# Sheet1.net
KiCad netlist of a schematic drawn in Altium Designer
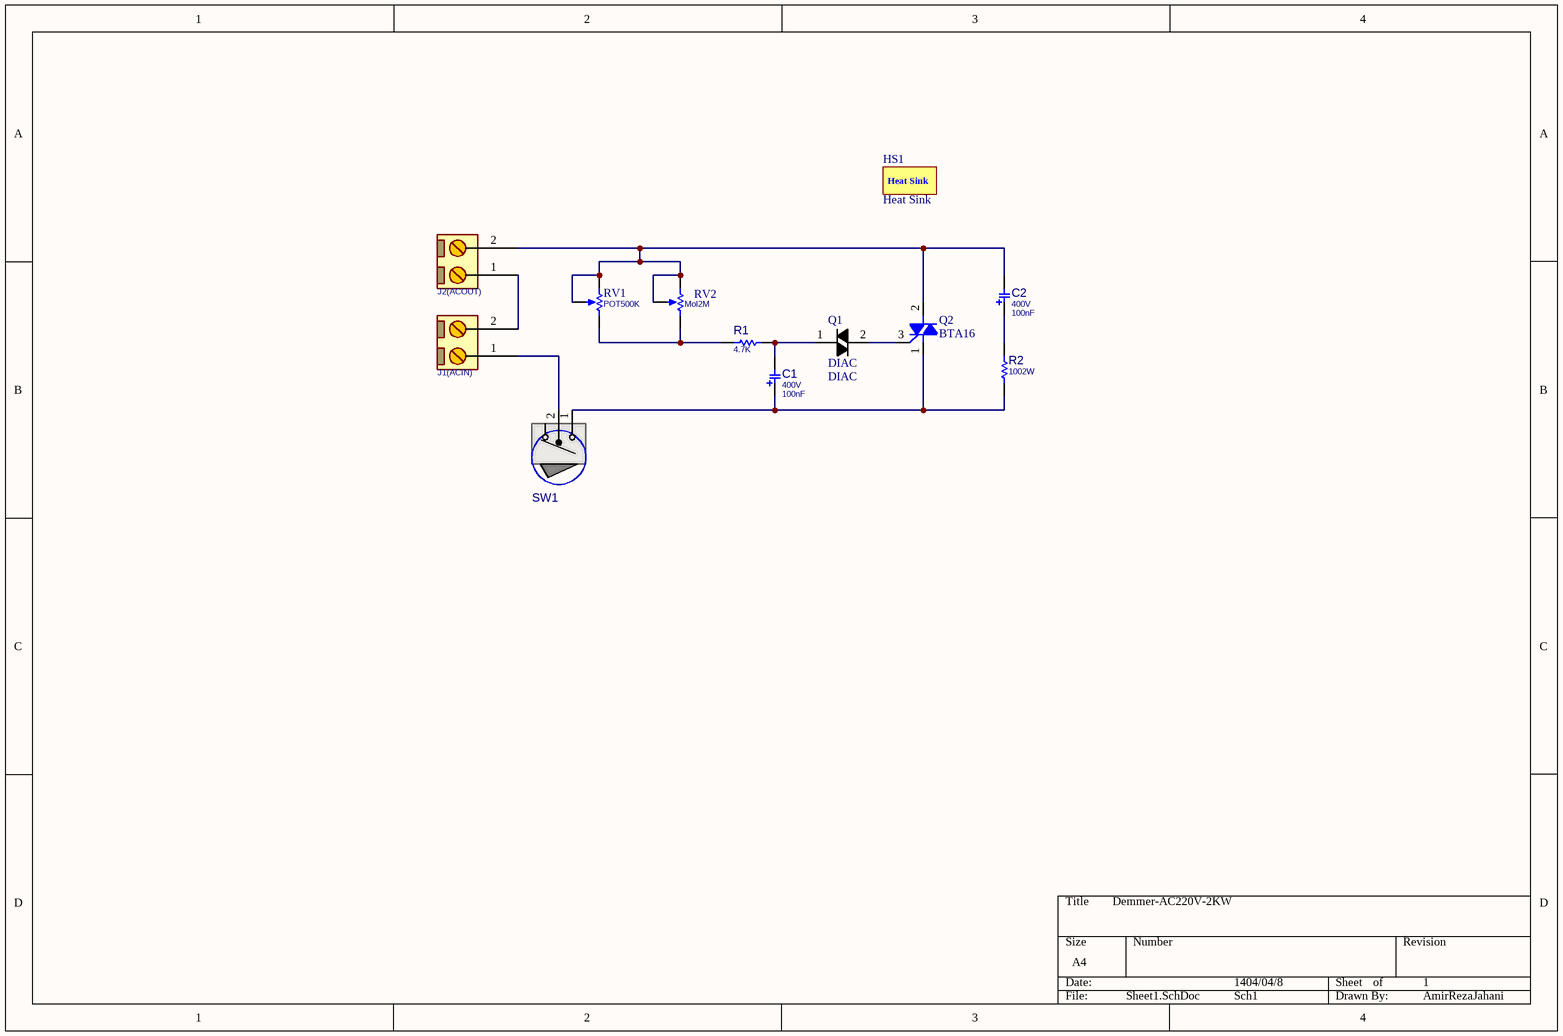
[diagram p0: Sheet1.SchDoc]

(export (version "E")
  (design (tool "Eeschema 10.0.6"))
  (components
    (comp (ref "C1")
      (value "100nF")
      (footprint "C_FLM_22X7H14")
      (description "CAP, THD, FILM,")
      (fields
        (field (name "MANF_P#") "MANF_PART#")
        (field (name "MANF") "MANF")
        (field (name "PARAM2") "400V")
      )
      (libsource (lib "passive_thd") (part "CAP_THD_FLM_0.33uF_400v"))
    )
    (comp (ref "C2")
      (value "100nF")
      (footprint "C_FLM_22X7H14")
      (description "CAP, THD, FILM,")
      (fields
        (field (name "MANF_P#") "MANF_PART#")
        (field (name "MANF") "MANF")
        (field (name "PARAM2") "400V")
      )
      (libsource (lib "passive_thd") (part "CAP_THD_FLM_0.33uF_400v"))
    )
    (comp (ref "HS1")
      (value "Heat Sink")
      (footprint "HeatSink PH51")
      (description "PH51 Heatsink")
      (libsource (lib "My_Library") (part "HeatSink PH51"))
    )
    (comp (ref "J1(ACIN)")
      (value "CONN_TB2")
      (footprint "TBG_2")
      (description "CONN, TERMINAL BLOCK, 5.08mm pitch")
      (libsource (lib "conn_terminalB") (part "CONN_TB2"))
    )
    (comp (ref "J2(ACOUT)")
      (value "CONN_TB2")
      (footprint "TBG_2")
      (description "CONN, TERMINAL BLOCK, 5.08mm pitch")
      (libsource (lib "conn_terminalB") (part "CONN_TB2"))
    )
    (comp (ref "Q1")
      (value "DIAC")
      (footprint "D_AX03_DO35")
      (description "Diac, 32VBO, DO-35")
      (fields (field (name "MANF_P#") "DB3") (field (name "MANF") "ST") (field (name "ALTIUM_VALUE") "DIAC"))
      (libsource (lib "triac_diac") (part "DIAC_DB3_DO35"))
    )
    (comp (ref "Q2")
      (value "BTA16")
      (footprint "TO220_3")
      (description "Triac, 800V, 16A, TO-220")
      (fields (field (name "MANF_P#") "BTA16-800CW") (field (name "MANF") "ST"))
      (libsource (lib "triac_diac") (part "TRIAC_BTA16-800_TO220"))
    )
    (comp (ref "R1")
      (value "4.7K")
      (footprint "R025W_AX04")
      (description "RESISTOR, THD")
      (fields (field (name "MANF_P#") "RK73H1ETTP4701F") (field (name "MANF") "KOA SPEER"))
      (libsource (lib "passive_thd") (part "RES_THD"))
    )
    (comp (ref "R2")
      (value "1002W")
      (footprint "R2W_AX08")
      (description "RESISTOR, THD")
      (fields (field (name "MANF_P#") "RK73H1ETTP4701F") (field (name "MANF") "KOA SPEER"))
      (libsource (lib "passive_thd") (part "RES_THD"))
    )
    (comp (ref "RV1")
      (value "POT500K")
      (footprint "VOL_R")
      (description "RESISTOR, THD, Potentiometer Volume")
      (libsource (lib "resistor_pot_trimmer") (part "RES_THD_POT_VOL"))
    )
    (comp (ref "RV2")
      (value "Mol2M")
      (footprint "POT_3296W")
      (description "RESISTOR, THD, Potentiometer")
      (libsource (lib "resistor_pot_trimmer") (part "RES_THD_POT_3296W"))
    )
    (comp (ref "SW1")
      (value "ToggleSwitch")
      (footprint "SWRCK_SPST_S_15X10")
      (description "SWITCH, Rocker, SPST, THD, 15x10.5mm")
      (libsource (lib "switch_rocker") (part "SWROK_SPST_R_15X10"))
    )
  )
  (nets
    (net (code "1") (name "Net-(C2-Pad1)") (class "Default")
      (node (ref "C2") (pin "1") (pinfunction "1_1") (pintype "passive"))
      (node (ref "R2") (pin "2") (pinfunction "2_2") (pintype "passive"))
    )
    (net (code "2") (name "Net-(J1(ACIN)-Pad2)") (class "Default")
      (node (ref "J1(ACIN)") (pin "2") (pinfunction "2_2") (pintype "passive"))
      (node (ref "J2(ACOUT)") (pin "1") (pinfunction "1_1") (pintype "passive"))
    )
    (net (code "3") (name "Net-(Q1-A1)") (class "Default")
      (node (ref "C1") (pin "2") (pinfunction "2_2") (pintype "passive"))
      (node (ref "Q1") (pin "1") (pinfunction "A1_1") (pintype "passive"))
      (node (ref "R1") (pin "2") (pinfunction "2_2") (pintype "passive"))
    )
    (net (code "4") (name "Net-(Q1-A2)") (class "Default")
      (node (ref "Q1") (pin "2") (pinfunction "A2_2") (pintype "passive"))
      (node (ref "Q2") (pin "3") (pinfunction "G_3") (pintype "passive"))
    )
    (net (code "5") (name "Net-(Q2-T1)") (class "Default")
      (node (ref "C1") (pin "1") (pinfunction "1_1") (pintype "passive"))
      (node (ref "Q2") (pin "1") (pinfunction "T1_1") (pintype "passive"))
      (node (ref "R2") (pin "1") (pinfunction "1_1") (pintype "passive"))
      (node (ref "SW1") (pin "1") (pinfunction "T1_1") (pintype "passive"))
    )
    (net (code "6") (name "Net-(Q2-T2)") (class "Default")
      (node (ref "C2") (pin "2") (pinfunction "2_2") (pintype "passive"))
      (node (ref "J2(ACOUT)") (pin "2") (pinfunction "2_2") (pintype "passive"))
      (node (ref "Q2") (pin "2") (pinfunction "T2_2") (pintype "passive"))
      (node (ref "RV1") (pin "1") (pinfunction "TOP_1") (pintype "passive"))
      (node (ref "RV1") (pin "2") (pinfunction "TAP_2") (pintype "passive"))
      (node (ref "RV2") (pin "1") (pinfunction "TOP_1") (pintype "passive"))
      (node (ref "RV2") (pin "2") (pinfunction "TAP_2") (pintype "passive"))
    )
    (net (code "7") (name "Net-(RV1-BOT)") (class "Default")
      (node (ref "R1") (pin "1") (pinfunction "1_1") (pintype "passive"))
      (node (ref "RV1") (pin "3") (pinfunction "BOT_3") (pintype "passive"))
      (node (ref "RV2") (pin "3") (pinfunction "BOT_3") (pintype "passive"))
    )
    (net (code "8") (name "Net-(SW1-COM)") (class "Default")
      (node (ref "J1(ACIN)") (pin "1") (pinfunction "1_1") (pintype "passive"))
      (node (ref "SW1") (pin "2") (pinfunction "COM_2") (pintype "passive"))
    )
  )
)
